# io_board.net
KiCad netlist of a schematic drawn in EAGLE
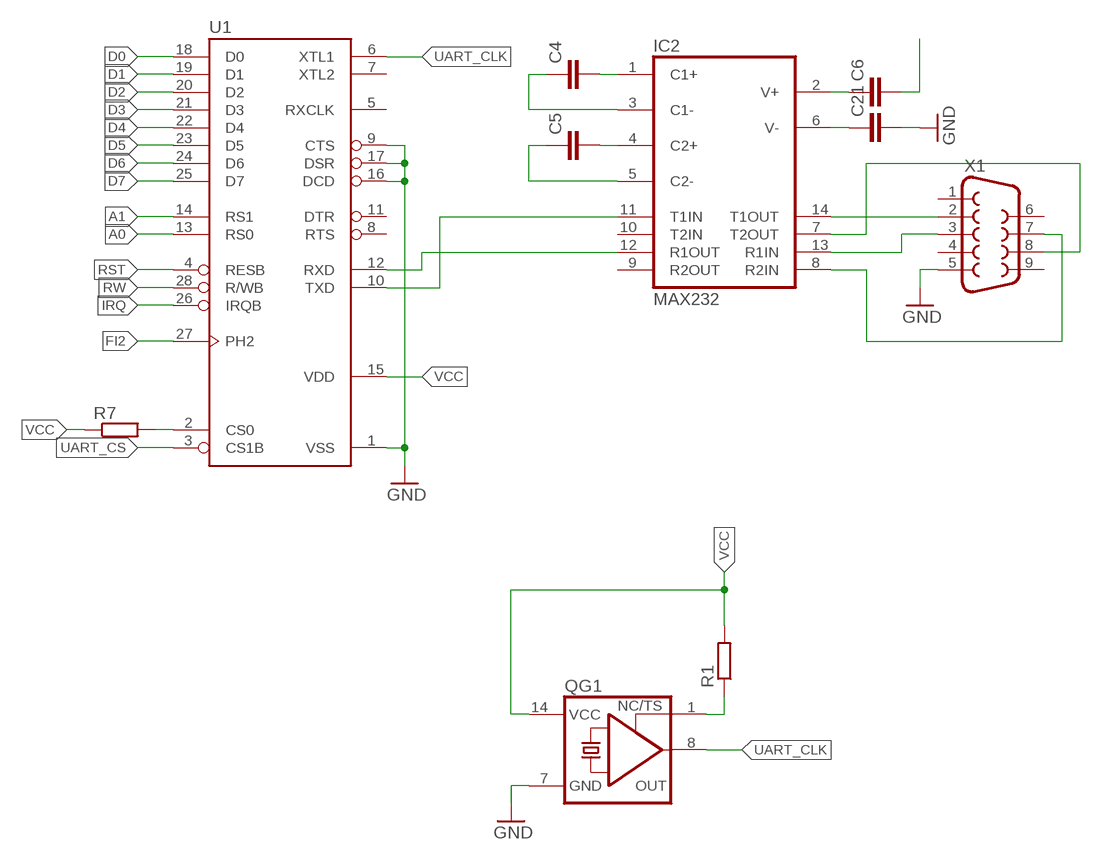
[diagram p0: schematic, sheet 1, part 1 of 2]
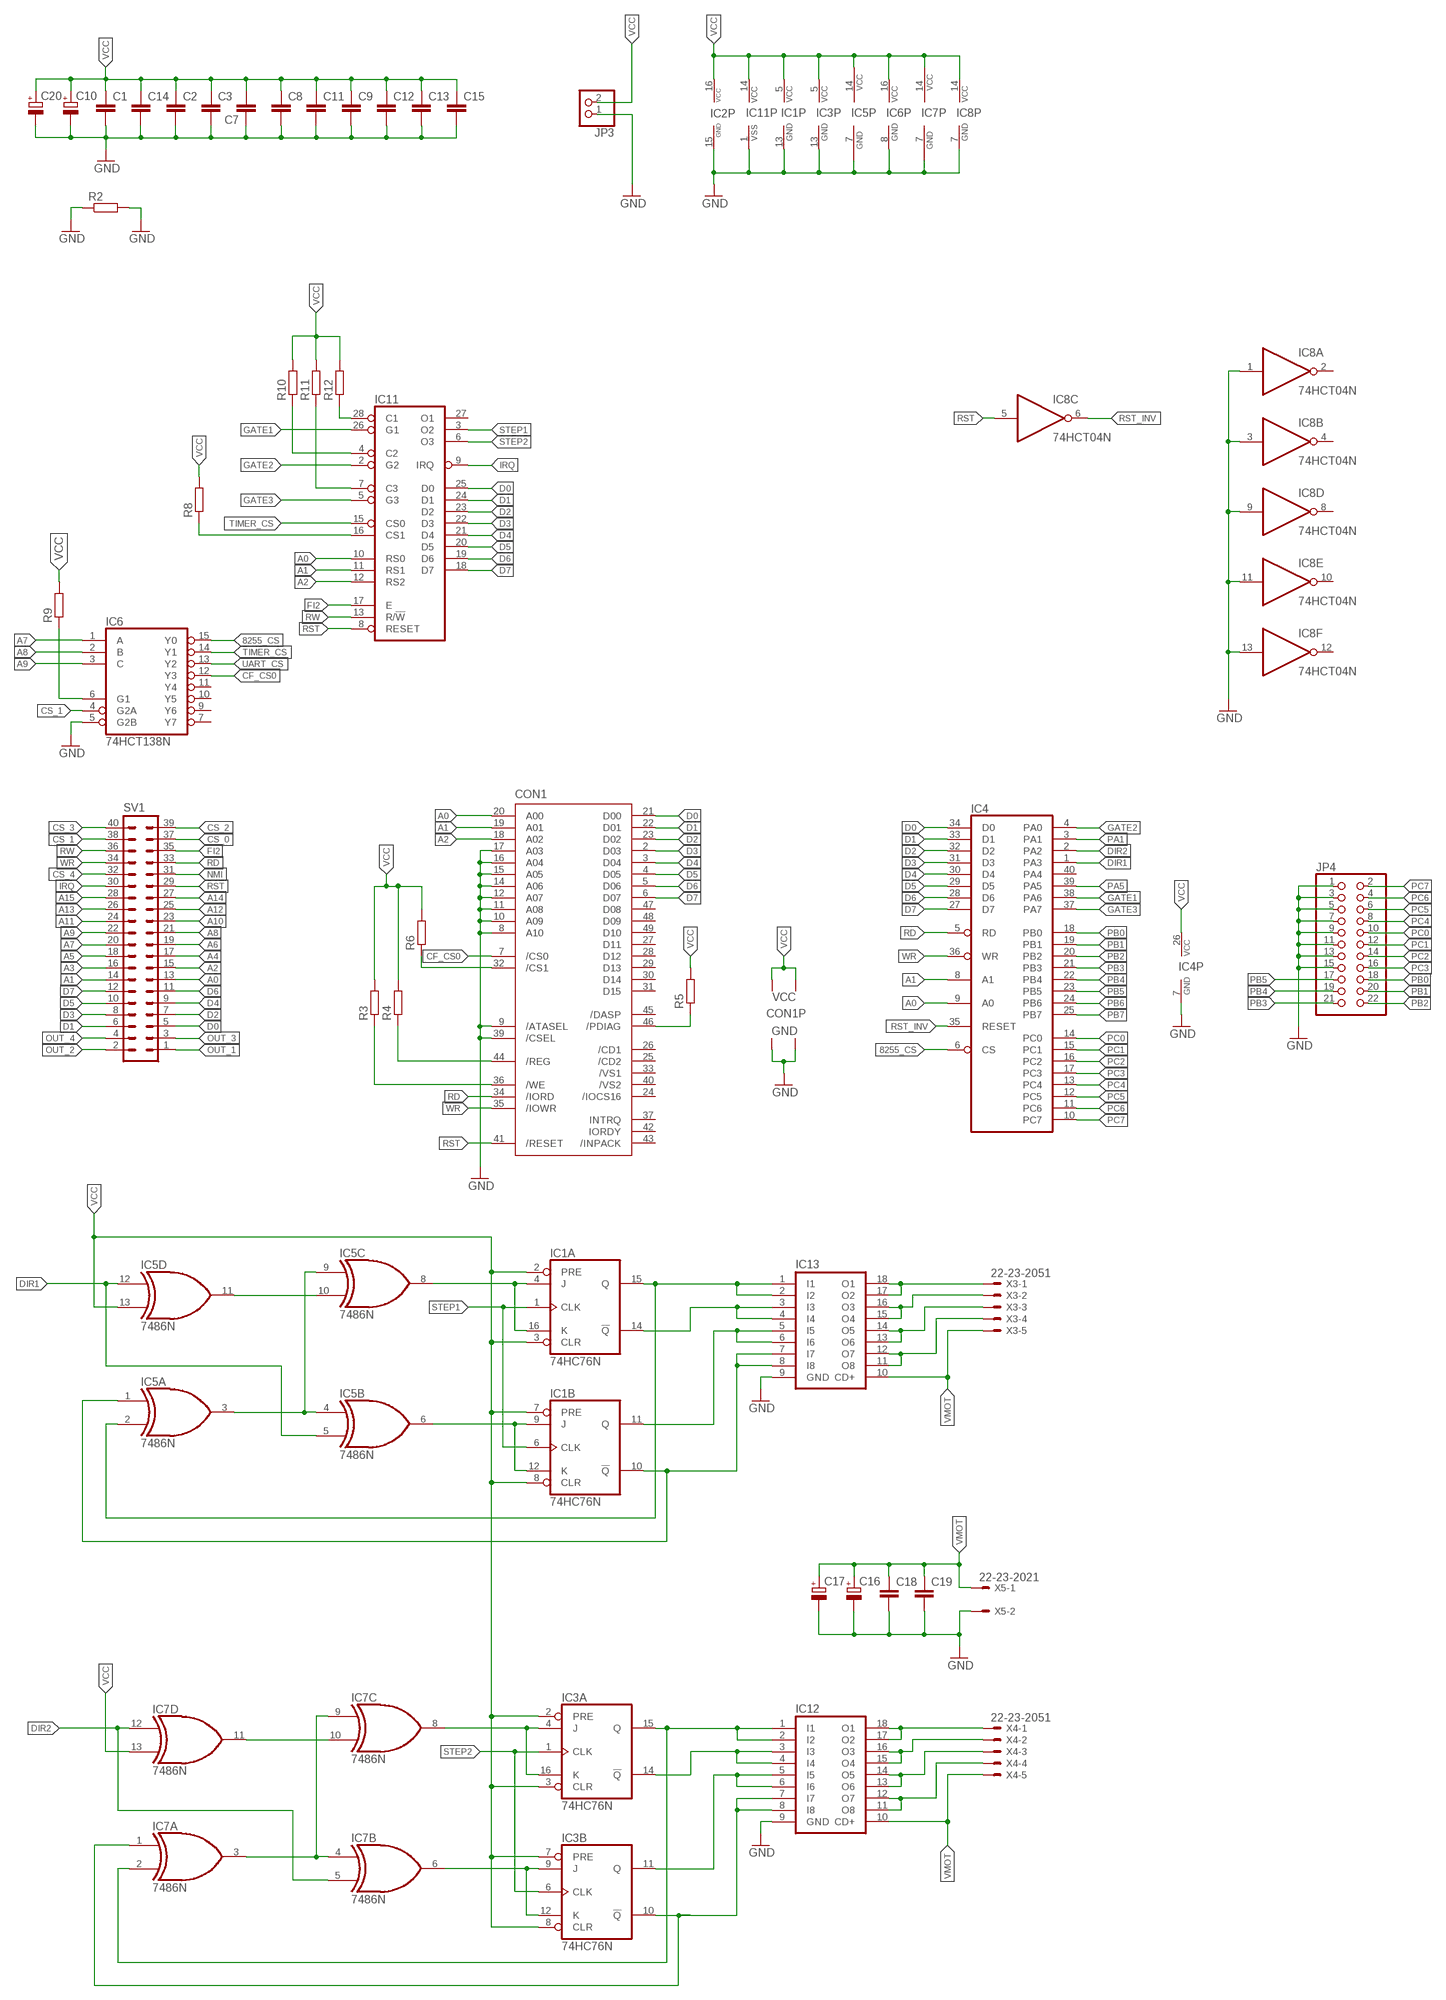
[diagram p1: schematic, sheet 1, part 2 of 2]

(export (version "E")
  (design (tool "Eeschema 10.0.6"))
  (components
    (comp (ref "C1")
      (value "C-EUC1206")
      (footprint "eagle-import:C1206")
      (libsource (lib "eagle-import") (part "C-EUC1206"))
    )
    (comp (ref "C2")
      (value "C-EUC1206")
      (footprint "eagle-import:C1206")
      (libsource (lib "eagle-import") (part "C-EUC1206"))
    )
    (comp (ref "C3")
      (value "C-EUC1206")
      (footprint "eagle-import:C1206")
      (libsource (lib "eagle-import") (part "C-EUC1206"))
    )
    (comp (ref "C4")
      (value "C-EUC0603")
      (footprint "eagle-import:C0603")
      (libsource (lib "eagle-import") (part "C-EUC0603"))
    )
    (comp (ref "C5")
      (value "C-EUC0603")
      (footprint "eagle-import:C0603")
      (libsource (lib "eagle-import") (part "C-EUC0603"))
    )
    (comp (ref "C6")
      (value "C-EUC0603")
      (footprint "eagle-import:C0603")
      (libsource (lib "eagle-import") (part "C-EUC0603"))
    )
    (comp (ref "C7")
      (value "C-EUC0603")
      (footprint "eagle-import:C0603")
      (libsource (lib "eagle-import") (part "C-EUC0603"))
    )
    (comp (ref "C8")
      (value "C-EUC0603")
      (footprint "eagle-import:C0603")
      (libsource (lib "eagle-import") (part "C-EUC0603"))
    )
    (comp (ref "C9")
      (value "C-EUC0603")
      (footprint "eagle-import:C0603")
      (libsource (lib "eagle-import") (part "C-EUC0603"))
    )
    (comp (ref "C10")
      (value "CPOL-EUE5-10.5")
      (footprint "eagle-import:E5-10,5")
      (libsource (lib "eagle-import") (part "CPOL-EUE5-10.5"))
    )
    (comp (ref "C11")
      (value "C-EU050-024X044")
      (footprint "eagle-import:C050-024X044")
      (libsource (lib "eagle-import") (part "C-EU050-024X044"))
    )
    (comp (ref "C12")
      (value "C-EUC0603")
      (footprint "eagle-import:C0603")
      (libsource (lib "eagle-import") (part "C-EUC0603"))
    )
    (comp (ref "C13")
      (value "C-EUC0603")
      (footprint "eagle-import:C0603")
      (libsource (lib "eagle-import") (part "C-EUC0603"))
    )
    (comp (ref "C14")
      (value "C-EUC1206")
      (footprint "eagle-import:C1206")
      (libsource (lib "eagle-import") (part "C-EUC1206"))
    )
    (comp (ref "C15")
      (value "C-EUC0603")
      (footprint "eagle-import:C0603")
      (libsource (lib "eagle-import") (part "C-EUC0603"))
    )
    (comp (ref "C16")
      (value "CPOL-EUE5-6")
      (footprint "eagle-import:E5-6")
      (libsource (lib "eagle-import") (part "CPOL-EUE5-6"))
    )
    (comp (ref "C17")
      (value "CPOL-EUE5-6")
      (footprint "eagle-import:E5-6")
      (libsource (lib "eagle-import") (part "CPOL-EUE5-6"))
    )
    (comp (ref "C18")
      (value "C-EUC0603")
      (footprint "eagle-import:C0603")
      (libsource (lib "eagle-import") (part "C-EUC0603"))
    )
    (comp (ref "C19")
      (value "C-EUC0603")
      (footprint "eagle-import:C0603")
      (libsource (lib "eagle-import") (part "C-EUC0603"))
    )
    (comp (ref "C20")
      (value "CPOL-EUSMCB")
      (footprint "eagle-import:SMC_B")
      (libsource (lib "eagle-import") (part "CPOL-EUSMCB"))
    )
    (comp (ref "C21")
      (value "C-EUC0603")
      (footprint "eagle-import:C0603")
      (libsource (lib "eagle-import") (part "C-EUC0603"))
    )
    (comp (ref "CON1")
      (value "CF-CARD-IDE_MODE")
      (footprint "eagle-import:MI20-50PD-SF")
      (libsource (lib "eagle-import") (part "CF-CARD-IDE_MODE"))
    )
    (comp (ref "IC1")
      (value "74HC76N")
      (footprint "eagle-import:DIL16")
      (libsource (lib "eagle-import") (part "7476NHC"))
    )
    (comp (ref "IC2")
      (value "MAX232")
      (footprint "eagle-import:DIL16")
      (fields (field (name "MF") "MAXIM") (field (name "MPN") "MAX232ACPE+"))
      (libsource (lib "eagle-import") (part "MAX232"))
    )
    (comp (ref "IC3")
      (value "74HC76N")
      (footprint "eagle-import:DIL16")
      (libsource (lib "eagle-import") (part "7476NHC"))
    )
    (comp (ref "IC4")
      (value "8255A")
      (footprint "eagle-import:DIL40")
      (libsource (lib "eagle-import") (part "8255A"))
    )
    (comp (ref "IC5")
      (value "7486N")
      (footprint "eagle-import:DIL14")
      (libsource (lib "eagle-import") (part "7486N"))
    )
    (comp (ref "IC6")
      (value "74HCT138N")
      (footprint "eagle-import:DIL16")
      (libsource (lib "eagle-import") (part "74138NHCT"))
    )
    (comp (ref "IC7")
      (value "7486N")
      (footprint "eagle-import:DIL14")
      (libsource (lib "eagle-import") (part "7486N"))
    )
    (comp (ref "IC8")
      (value "74HCT04N")
      (footprint "eagle-import:DIL14")
      (libsource (lib "eagle-import") (part "7404NHCT"))
    )
    (comp (ref "IC11")
      (value "6840")
      (footprint "eagle-import:DIL28")
      (libsource (lib "eagle-import") (part "6840"))
    )
    (comp (ref "IC12")
      (value "ULN2803A")
      (footprint "eagle-import:DIL18")
      (libsource (lib "eagle-import") (part "ULN2803A"))
    )
    (comp (ref "IC13")
      (value "ULN2803A")
      (footprint "eagle-import:DIL18")
      (libsource (lib "eagle-import") (part "ULN2803A"))
    )
    (comp (ref "JP3")
      (value "PINHD-1X2/90")
      (footprint "eagle-import:1X02_90")
      (libsource (lib "eagle-import") (part "PINHD-1X2/90"))
    )
    (comp (ref "JP4")
      (value "PINHD-2X11")
      (footprint "eagle-import:2X11")
      (libsource (lib "eagle-import") (part "PINHD-2X11"))
    )
    (comp (ref "QG1")
      (value "XO-14")
      (footprint "eagle-import:DIL14S")
      (libsource (lib "eagle-import") (part "XO-14"))
    )
    (comp (ref "R1")
      (value "R-EU_R1206")
      (footprint "eagle-import:R1206")
      (libsource (lib "eagle-import") (part "R-EU_R1206"))
    )
    (comp (ref "R2")
      (value "R-EU_M1206")
      (footprint "eagle-import:M1206")
      (libsource (lib "eagle-import") (part "R-EU_M1206"))
    )
    (comp (ref "R3")
      (value "R-EU_R0603")
      (footprint "eagle-import:R0603")
      (libsource (lib "eagle-import") (part "R-EU_R0603"))
    )
    (comp (ref "R4")
      (value "R-EU_R0603")
      (footprint "eagle-import:R0603")
      (libsource (lib "eagle-import") (part "R-EU_R0603"))
    )
    (comp (ref "R5")
      (value "R-EU_R0603")
      (footprint "eagle-import:R0603")
      (libsource (lib "eagle-import") (part "R-EU_R0603"))
    )
    (comp (ref "R6")
      (value "R-EU_R0603")
      (footprint "eagle-import:R0603")
      (libsource (lib "eagle-import") (part "R-EU_R0603"))
    )
    (comp (ref "R7")
      (value "R-EU_R0603")
      (footprint "eagle-import:R0603")
      (libsource (lib "eagle-import") (part "R-EU_R0603"))
    )
    (comp (ref "R8")
      (value "R-EU_R0402")
      (footprint "eagle-import:R0402")
      (libsource (lib "eagle-import") (part "R-EU_R0402"))
    )
    (comp (ref "R9")
      (value "R-EU_R1206")
      (footprint "eagle-import:R1206")
      (libsource (lib "eagle-import") (part "R-EU_R1206"))
    )
    (comp (ref "R10")
      (value "R-EU_R0603")
      (footprint "eagle-import:R0603")
      (libsource (lib "eagle-import") (part "R-EU_R0603"))
    )
    (comp (ref "R11")
      (value "R-EU_0204/7")
      (footprint "eagle-import:0204_7")
      (libsource (lib "eagle-import") (part "R-EU_0204/7"))
    )
    (comp (ref "R12")
      (value "R-EU_0204/5")
      (footprint "eagle-import:0204_5")
      (libsource (lib "eagle-import") (part "R-EU_0204/5"))
    )
    (comp (ref "SV1")
      (value "ML40L")
      (footprint "eagle-import:ML40L")
      (libsource (lib "eagle-import") (part "ML40L"))
    )
    (comp (ref "U1")
      (value "G65SC51P")
      (footprint "eagle-import:DIP-28")
      (libsource (lib "eagle-import") (part "G65SC51P"))
    )
    (comp (ref "X1")
      (value "F09HP")
      (footprint "eagle-import:F09HP")
      (libsource (lib "eagle-import") (part "F09HP"))
    )
    (comp (ref "X3")
      (value "22-23-2051")
      (footprint "eagle-import:22-23-2051")
      (fields (field (name "MF") "MOLEX"))
      (libsource (lib "eagle-import") (part "22-23-2051"))
    )
    (comp (ref "X4")
      (value "22-23-2051")
      (footprint "eagle-import:22-23-2051")
      (fields (field (name "MF") "MOLEX"))
      (libsource (lib "eagle-import") (part "22-23-2051"))
    )
    (comp (ref "X5")
      (value "22-23-2021")
      (footprint "eagle-import:22-23-2021")
      (fields (field (name "MF") "MOLEX"))
      (libsource (lib "eagle-import") (part "22-23-2021"))
    )
  )
  (nets
    (net (code "1") (name "8255_CS") (class "Default")
      (node (ref "IC4") (pin "6") (pinfunction "CS_6") (pintype "input"))
      (node (ref "IC6") (pin "15") (pinfunction "Y0_15") (pintype "output"))
    )
    (net (code "2") (name "A0") (class "Default")
      (node (ref "CON1") (pin "20") (pinfunction "A00_20") (pintype "input"))
      (node (ref "IC11") (pin "10") (pinfunction "RS0_10") (pintype "input"))
      (node (ref "IC4") (pin "9") (pinfunction "A0_9") (pintype "input"))
      (node (ref "SV1") (pin "13") (pinfunction "13_13") (pintype "passive"))
      (node (ref "U1") (pin "13") (pinfunction "RS0_13") (pintype "input"))
    )
    (net (code "3") (name "A1") (class "Default")
      (node (ref "CON1") (pin "19") (pinfunction "A01_19") (pintype "input"))
      (node (ref "IC11") (pin "11") (pinfunction "RS1_11") (pintype "input"))
      (node (ref "IC4") (pin "8") (pinfunction "A1_8") (pintype "input"))
      (node (ref "SV1") (pin "14") (pinfunction "14_14") (pintype "passive"))
      (node (ref "U1") (pin "14") (pinfunction "RS1_14") (pintype "input"))
    )
    (net (code "4") (name "A2") (class "Default")
      (node (ref "CON1") (pin "18") (pinfunction "A02_18") (pintype "input"))
      (node (ref "IC11") (pin "12") (pinfunction "RS2_12") (pintype "input"))
      (node (ref "SV1") (pin "15") (pinfunction "15_15") (pintype "passive"))
    )
    (net (code "5") (name "A3") (class "Default")
      (node (ref "SV1") (pin "16") (pinfunction "16_16") (pintype "passive"))
    )
    (net (code "6") (name "A4") (class "Default")
      (node (ref "SV1") (pin "17") (pinfunction "17_17") (pintype "passive"))
    )
    (net (code "7") (name "A5") (class "Default")
      (node (ref "SV1") (pin "18") (pinfunction "18_18") (pintype "passive"))
    )
    (net (code "8") (name "A6") (class "Default")
      (node (ref "SV1") (pin "19") (pinfunction "19_19") (pintype "passive"))
    )
    (net (code "9") (name "A7") (class "Default")
      (node (ref "IC6") (pin "1") (pinfunction "A_1") (pintype "input"))
      (node (ref "SV1") (pin "20") (pinfunction "20_20") (pintype "passive"))
    )
    (net (code "10") (name "A8") (class "Default")
      (node (ref "IC6") (pin "2") (pinfunction "B_2") (pintype "input"))
      (node (ref "SV1") (pin "21") (pinfunction "21_21") (pintype "passive"))
    )
    (net (code "11") (name "A9") (class "Default")
      (node (ref "IC6") (pin "3") (pinfunction "C_3") (pintype "input"))
      (node (ref "SV1") (pin "22") (pinfunction "22_22") (pintype "passive"))
    )
    (net (code "12") (name "A10") (class "Default")
      (node (ref "SV1") (pin "23") (pinfunction "23_23") (pintype "passive"))
    )
    (net (code "13") (name "A11") (class "Default")
      (node (ref "SV1") (pin "24") (pinfunction "24_24") (pintype "passive"))
    )
    (net (code "14") (name "A12") (class "Default")
      (node (ref "SV1") (pin "25") (pinfunction "25_25") (pintype "passive"))
    )
    (net (code "15") (name "A13") (class "Default")
      (node (ref "SV1") (pin "26") (pinfunction "26_26") (pintype "passive"))
    )
    (net (code "16") (name "A14") (class "Default")
      (node (ref "SV1") (pin "27") (pinfunction "27_27") (pintype "passive"))
    )
    (net (code "17") (name "A15") (class "Default")
      (node (ref "SV1") (pin "28") (pinfunction "28_28") (pintype "passive"))
    )
    (net (code "18") (name "CF_CS0") (class "Default")
      (node (ref "CON1") (pin "7") (pinfunction "/CS0_7") (pintype "input"))
      (node (ref "IC6") (pin "12") (pinfunction "Y3_12") (pintype "output"))
    )
    (net (code "19") (name "CS_0") (class "Default")
      (node (ref "SV1") (pin "37") (pinfunction "37_37") (pintype "passive"))
    )
    (net (code "20") (name "CS_1") (class "Default")
      (node (ref "IC6") (pin "4") (pinfunction "G2A_4") (pintype "input"))
      (node (ref "SV1") (pin "38") (pinfunction "38_38") (pintype "passive"))
    )
    (net (code "21") (name "CS_2") (class "Default")
      (node (ref "SV1") (pin "39") (pinfunction "39_39") (pintype "passive"))
    )
    (net (code "22") (name "CS_3") (class "Default")
      (node (ref "SV1") (pin "40") (pinfunction "40_40") (pintype "passive"))
    )
    (net (code "23") (name "CS_4") (class "Default")
      (node (ref "SV1") (pin "32") (pinfunction "32_32") (pintype "passive"))
    )
    (net (code "24") (name "D0") (class "Default")
      (node (ref "CON1") (pin "21") (pinfunction "D00_21") (pintype "bidirectional"))
      (node (ref "IC11") (pin "25") (pinfunction "D0_25") (pintype "bidirectional"))
      (node (ref "IC4") (pin "34") (pinfunction "D0_34") (pintype "bidirectional"))
      (node (ref "SV1") (pin "5") (pinfunction "5_5") (pintype "passive"))
      (node (ref "U1") (pin "18") (pinfunction "D0_18") (pintype "bidirectional"))
    )
    (net (code "25") (name "D1") (class "Default")
      (node (ref "CON1") (pin "22") (pinfunction "D01_22") (pintype "bidirectional"))
      (node (ref "IC11") (pin "24") (pinfunction "D1_24") (pintype "bidirectional"))
      (node (ref "IC4") (pin "33") (pinfunction "D1_33") (pintype "bidirectional"))
      (node (ref "SV1") (pin "6") (pinfunction "6_6") (pintype "passive"))
      (node (ref "U1") (pin "19") (pinfunction "D1_19") (pintype "bidirectional"))
    )
    (net (code "26") (name "D2") (class "Default")
      (node (ref "CON1") (pin "23") (pinfunction "D02_23") (pintype "bidirectional"))
      (node (ref "IC11") (pin "23") (pinfunction "D2_23") (pintype "bidirectional"))
      (node (ref "IC4") (pin "32") (pinfunction "D2_32") (pintype "bidirectional"))
      (node (ref "SV1") (pin "7") (pinfunction "7_7") (pintype "passive"))
      (node (ref "U1") (pin "20") (pinfunction "D2_20") (pintype "bidirectional"))
    )
    (net (code "27") (name "D3") (class "Default")
      (node (ref "CON1") (pin "2") (pinfunction "D03_2") (pintype "bidirectional"))
      (node (ref "IC11") (pin "22") (pinfunction "D3_22") (pintype "bidirectional"))
      (node (ref "IC4") (pin "31") (pinfunction "D3_31") (pintype "bidirectional"))
      (node (ref "SV1") (pin "8") (pinfunction "8_8") (pintype "passive"))
      (node (ref "U1") (pin "21") (pinfunction "D3_21") (pintype "bidirectional"))
    )
    (net (code "28") (name "D4") (class "Default")
      (node (ref "CON1") (pin "3") (pinfunction "D04_3") (pintype "bidirectional"))
      (node (ref "IC11") (pin "21") (pinfunction "D4_21") (pintype "bidirectional"))
      (node (ref "IC4") (pin "30") (pinfunction "D4_30") (pintype "bidirectional"))
      (node (ref "SV1") (pin "9") (pinfunction "9_9") (pintype "passive"))
      (node (ref "U1") (pin "22") (pinfunction "D4_22") (pintype "bidirectional"))
    )
    (net (code "29") (name "D5") (class "Default")
      (node (ref "CON1") (pin "4") (pinfunction "D05_4") (pintype "bidirectional"))
      (node (ref "IC11") (pin "20") (pinfunction "D5_20") (pintype "bidirectional"))
      (node (ref "IC4") (pin "29") (pinfunction "D5_29") (pintype "bidirectional"))
      (node (ref "SV1") (pin "10") (pinfunction "10_10") (pintype "passive"))
      (node (ref "U1") (pin "23") (pinfunction "D5_23") (pintype "bidirectional"))
    )
    (net (code "30") (name "D6") (class "Default")
      (node (ref "CON1") (pin "5") (pinfunction "D06_5") (pintype "bidirectional"))
      (node (ref "IC11") (pin "19") (pinfunction "D6_19") (pintype "bidirectional"))
      (node (ref "IC4") (pin "28") (pinfunction "D6_28") (pintype "bidirectional"))
      (node (ref "SV1") (pin "11") (pinfunction "11_11") (pintype "passive"))
      (node (ref "U1") (pin "24") (pinfunction "D6_24") (pintype "bidirectional"))
    )
    (net (code "31") (name "D7") (class "Default")
      (node (ref "CON1") (pin "6") (pinfunction "D07_6") (pintype "bidirectional"))
      (node (ref "IC11") (pin "18") (pinfunction "D7_18") (pintype "bidirectional"))
      (node (ref "IC4") (pin "27") (pinfunction "D7_27") (pintype "bidirectional"))
      (node (ref "SV1") (pin "12") (pinfunction "12_12") (pintype "passive"))
      (node (ref "U1") (pin "25") (pinfunction "D7_25") (pintype "bidirectional"))
    )
    (net (code "32") (name "DIR1") (class "Default")
      (node (ref "IC4") (pin "1") (pinfunction "PA3_1") (pintype "bidirectional"))
      (node (ref "IC5") (pin "12") (pinfunction "I0_12") (pintype "input"))
      (node (ref "IC5") (pin "5") (pinfunction "I1_5") (pintype "input"))
    )
    (net (code "33") (name "DIR2") (class "Default")
      (node (ref "IC4") (pin "2") (pinfunction "PA2_2") (pintype "bidirectional"))
      (node (ref "IC7") (pin "12") (pinfunction "I0_12") (pintype "input"))
      (node (ref "IC7") (pin "5") (pinfunction "I1_5") (pintype "input"))
    )
    (net (code "34") (name "FI2") (class "Default")
      (node (ref "IC11") (pin "17") (pinfunction "E_17") (pintype "input"))
      (node (ref "SV1") (pin "35") (pinfunction "35_35") (pintype "passive"))
      (node (ref "U1") (pin "27") (pinfunction "PH2_27") (pintype "power_in"))
    )
    (net (code "35") (name "GATE1") (class "Default")
      (node (ref "IC11") (pin "26") (pinfunction "G1_26") (pintype "input"))
      (node (ref "IC4") (pin "38") (pinfunction "PA6_38") (pintype "bidirectional"))
    )
    (net (code "36") (name "GATE2") (class "Default")
      (node (ref "IC11") (pin "2") (pinfunction "G2_2") (pintype "input"))
      (node (ref "IC4") (pin "4") (pinfunction "PA0_4") (pintype "bidirectional"))
    )
    (net (code "37") (name "GATE3") (class "Default")
      (node (ref "IC11") (pin "5") (pinfunction "G3_5") (pintype "input"))
      (node (ref "IC4") (pin "37") (pinfunction "PA7_37") (pintype "bidirectional"))
    )
    (net (code "38") (name "GND") (class "Default")
      (node (ref "C1") (pin "2") (pinfunction "2_2") (pintype "passive"))
      (node (ref "C10") (pin "-") (pinfunction "-_-") (pintype "passive"))
      (node (ref "C11") (pin "2") (pinfunction "2_2") (pintype "passive"))
      (node (ref "C12") (pin "2") (pinfunction "2_2") (pintype "passive"))
      (node (ref "C13") (pin "2") (pinfunction "2_2") (pintype "passive"))
      (node (ref "C14") (pin "2") (pinfunction "2_2") (pintype "passive"))
      (node (ref "C15") (pin "2") (pinfunction "2_2") (pintype "passive"))
      (node (ref "C16") (pin "-") (pinfunction "-_-") (pintype "passive"))
      (node (ref "C17") (pin "-") (pinfunction "-_-") (pintype "passive"))
      (node (ref "C18") (pin "2") (pinfunction "2_2") (pintype "passive"))
      (node (ref "C19") (pin "2") (pinfunction "2_2") (pintype "passive"))
      (node (ref "C2") (pin "2") (pinfunction "2_2") (pintype "passive"))
      (node (ref "C20") (pin "-") (pinfunction "-_-") (pintype "passive"))
      (node (ref "C21") (pin "2") (pinfunction "2_2") (pintype "passive"))
      (node (ref "C3") (pin "2") (pinfunction "2_2") (pintype "passive"))
      (node (ref "C7") (pin "1") (pinfunction "1_1") (pintype "passive"))
      (node (ref "C8") (pin "2") (pinfunction "2_2") (pintype "passive"))
      (node (ref "C9") (pin "2") (pinfunction "2_2") (pintype "passive"))
      (node (ref "CON1") (pin "1") (pinfunction "GND1_1") (pintype "power_in"))
      (node (ref "CON1") (pin "10") (pinfunction "A09_10") (pintype "input"))
      (node (ref "CON1") (pin "11") (pinfunction "A08_11") (pintype "input"))
      (node (ref "CON1") (pin "12") (pinfunction "A07_12") (pintype "input"))
      (node (ref "CON1") (pin "14") (pinfunction "A06_14") (pintype "input"))
      (node (ref "CON1") (pin "15") (pinfunction "A05_15") (pintype "input"))
      (node (ref "CON1") (pin "16") (pinfunction "A04_16") (pintype "input"))
      (node (ref "CON1") (pin "17") (pinfunction "A03_17") (pintype "input"))
      (node (ref "CON1") (pin "39") (pinfunction "/CSEL_39") (pintype "input"))
      (node (ref "CON1") (pin "50") (pinfunction "GND2_50") (pintype "power_in"))
      (node (ref "CON1") (pin "8") (pinfunction "A10_8") (pintype "input"))
      (node (ref "CON1") (pin "9") (pinfunction "/ATASEL_9") (pintype "input"))
      (node (ref "IC1") (pin "13") (pinfunction "GND_13") (pintype "power_in"))
      (node (ref "IC11") (pin "1") (pinfunction "VSS_1") (pintype "power_in"))
      (node (ref "IC12") (pin "9") (pinfunction "GND_9") (pintype "power_in"))
      (node (ref "IC13") (pin "9") (pinfunction "GND_9") (pintype "power_in"))
      (node (ref "IC2") (pin "15") (pinfunction "GND_15") (pintype "power_in"))
      (node (ref "IC3") (pin "13") (pinfunction "GND_13") (pintype "power_in"))
      (node (ref "IC4") (pin "7") (pinfunction "GND_7") (pintype "power_in"))
      (node (ref "IC5") (pin "7") (pinfunction "GND_7") (pintype "power_in"))
      (node (ref "IC6") (pin "5") (pinfunction "G2B_5") (pintype "input"))
      (node (ref "IC6") (pin "8") (pinfunction "GND_8") (pintype "power_in"))
      (node (ref "IC7") (pin "7") (pinfunction "GND_7") (pintype "power_in"))
      (node (ref "IC8") (pin "1") (pinfunction "I_1") (pintype "input"))
      (node (ref "IC8") (pin "11") (pinfunction "I_11") (pintype "input"))
      (node (ref "IC8") (pin "13") (pinfunction "I_13") (pintype "input"))
      (node (ref "IC8") (pin "3") (pinfunction "I_3") (pintype "input"))
      (node (ref "IC8") (pin "7") (pinfunction "GND_7") (pintype "power_in"))
      (node (ref "IC8") (pin "9") (pinfunction "I_9") (pintype "input"))
      (node (ref "JP3") (pin "1") (pinfunction "1_1") (pintype "passive"))
      (node (ref "JP4") (pin "1") (pinfunction "1_1") (pintype "passive"))
      (node (ref "JP4") (pin "11") (pinfunction "11_11") (pintype "passive"))
      (node (ref "JP4") (pin "13") (pinfunction "13_13") (pintype "passive"))
      (node (ref "JP4") (pin "15") (pinfunction "15_15") (pintype "passive"))
      (node (ref "JP4") (pin "3") (pinfunction "3_3") (pintype "passive"))
      (node (ref "JP4") (pin "5") (pinfunction "5_5") (pintype "passive"))
      (node (ref "JP4") (pin "7") (pinfunction "7_7") (pintype "passive"))
      (node (ref "JP4") (pin "9") (pinfunction "9_9") (pintype "passive"))
      (node (ref "QG1") (pin "7") (pinfunction "GND_7") (pintype "power_in"))
      (node (ref "R2") (pin "1") (pinfunction "1_1") (pintype "passive"))
      (node (ref "R2") (pin "2") (pinfunction "2_2") (pintype "passive"))
      (node (ref "U1") (pin "1") (pinfunction "VSS_1") (pintype "power_in"))
      (node (ref "U1") (pin "16") (pinfunction "DCD_16") (pintype "input"))
      (node (ref "U1") (pin "17") (pinfunction "DSR_17") (pintype "input"))
      (node (ref "U1") (pin "9") (pinfunction "CTS_9") (pintype "input"))
      (node (ref "X1") (pin "5") (pinfunction "5_5") (pintype "passive"))
      (node (ref "X5") (pin "2") (pinfunction "S_2") (pintype "passive"))
    )
    (net (code "39") (name "IRQ") (class "Default")
      (node (ref "IC11") (pin "9") (pinfunction "IRQ_9") (pintype "open_collector"))
      (node (ref "SV1") (pin "30") (pinfunction "30_30") (pintype "passive"))
      (node (ref "U1") (pin "26") (pinfunction "IRQB_26") (pintype "output"))
    )
    (net (code "40") (name "NMI") (class "Default")
      (node (ref "SV1") (pin "31") (pinfunction "31_31") (pintype "passive"))
    )
    (net (code "41") (name "Net-(CON1A-{slash}CS1)") (class "Default")
      (node (ref "CON1") (pin "32") (pinfunction "/CS1_32") (pintype "input"))
      (node (ref "R6") (pin "1") (pinfunction "1_1") (pintype "passive"))
    )
    (net (code "42") (name "Net-(CON1A-{slash}PDIAG)") (class "Default")
      (node (ref "CON1") (pin "46") (pinfunction "/PDIAG_46") (pintype "bidirectional"))
      (node (ref "R5") (pin "1") (pinfunction "1_1") (pintype "passive"))
    )
    (net (code "43") (name "Net-(CON1A-{slash}REG)") (class "Default")
      (node (ref "CON1") (pin "44") (pinfunction "/REG_44") (pintype "input"))
      (node (ref "R4") (pin "1") (pinfunction "1_1") (pintype "passive"))
    )
    (net (code "44") (name "Net-(CON1A-{slash}WE)") (class "Default")
      (node (ref "CON1") (pin "36") (pinfunction "/WE_36") (pintype "input"))
      (node (ref "R3") (pin "1") (pinfunction "1_1") (pintype "passive"))
    )
    (net (code "45") (name "Net-(IC1A-J)") (class "Default")
      (node (ref "IC1") (pin "16") (pinfunction "K_16") (pintype "input"))
      (node (ref "IC1") (pin "4") (pinfunction "J_4") (pintype "input"))
      (node (ref "IC5") (pin "8") (pinfunction "O_8") (pintype "output"))
    )
    (net (code "46") (name "Net-(IC1B-J)") (class "Default")
      (node (ref "IC1") (pin "12") (pinfunction "K_12") (pintype "input"))
      (node (ref "IC1") (pin "9") (pinfunction "J_9") (pintype "input"))
      (node (ref "IC5") (pin "6") (pinfunction "O_6") (pintype "output"))
    )
    (net (code "47") (name "Net-(IC2A-C1+)") (class "Default")
      (node (ref "C4") (pin "2") (pinfunction "2_2") (pintype "passive"))
      (node (ref "IC2") (pin "1") (pinfunction "C1+_1") (pintype "bidirectional"))
    )
    (net (code "48") (name "Net-(IC2A-C1-)") (class "Default")
      (node (ref "C4") (pin "1") (pinfunction "1_1") (pintype "passive"))
      (node (ref "IC2") (pin "3") (pinfunction "C1-_3") (pintype "bidirectional"))
    )
    (net (code "49") (name "Net-(IC2A-C2+)") (class "Default")
      (node (ref "C5") (pin "2") (pinfunction "2_2") (pintype "passive"))
      (node (ref "IC2") (pin "4") (pinfunction "C2+_4") (pintype "bidirectional"))
    )
    (net (code "50") (name "Net-(IC2A-C2-)") (class "Default")
      (node (ref "C5") (pin "1") (pinfunction "1_1") (pintype "passive"))
      (node (ref "IC2") (pin "5") (pinfunction "C2-_5") (pintype "bidirectional"))
    )
    (net (code "51") (name "Net-(IC2A-R1IN)") (class "Default")
      (node (ref "IC2") (pin "13") (pinfunction "R1IN_13") (pintype "input"))
      (node (ref "X1") (pin "3") (pinfunction "3_3") (pintype "passive"))
    )
    (net (code "52") (name "Net-(IC2A-R1OUT)") (class "Default")
      (node (ref "IC2") (pin "12") (pinfunction "R1OUT_12") (pintype "output"))
      (node (ref "U1") (pin "12") (pinfunction "RXD_12") (pintype "input"))
    )
    (net (code "53") (name "Net-(IC2A-R2IN)") (class "Default")
      (node (ref "IC2") (pin "8") (pinfunction "R2IN_8") (pintype "input"))
      (node (ref "X1") (pin "7") (pinfunction "7_7") (pintype "passive"))
    )
    (net (code "54") (name "Net-(IC2A-T1IN)") (class "Default")
      (node (ref "IC2") (pin "11") (pinfunction "T1IN_11") (pintype "input"))
      (node (ref "U1") (pin "10") (pinfunction "TXD_10") (pintype "output"))
    )
    (net (code "55") (name "Net-(IC2A-T1OUT)") (class "Default")
      (node (ref "IC2") (pin "14") (pinfunction "T1OUT_14") (pintype "output"))
      (node (ref "X1") (pin "2") (pinfunction "2_2") (pintype "passive"))
    )
    (net (code "56") (name "Net-(IC2A-T2OUT)") (class "Default")
      (node (ref "IC2") (pin "7") (pinfunction "T2OUT_7") (pintype "output"))
      (node (ref "X1") (pin "8") (pinfunction "8_8") (pintype "passive"))
    )
    (net (code "57") (name "Net-(IC2A-V+)") (class "Default")
      (node (ref "C6") (pin "1") (pinfunction "1_1") (pintype "passive"))
      (node (ref "IC2") (pin "2") (pinfunction "V+_2") (pintype "bidirectional"))
    )
    (net (code "58") (name "Net-(IC2A-V-)") (class "Default")
      (node (ref "C21") (pin "1") (pinfunction "1_1") (pintype "passive"))
      (node (ref "IC2") (pin "6") (pinfunction "V-_6") (pintype "bidirectional"))
    )
    (net (code "59") (name "Net-(IC3A-J)") (class "Default")
      (node (ref "IC3") (pin "16") (pinfunction "K_16") (pintype "input"))
      (node (ref "IC3") (pin "4") (pinfunction "J_4") (pintype "input"))
      (node (ref "IC7") (pin "8") (pinfunction "O_8") (pintype "output"))
    )
    (net (code "60") (name "Net-(IC3B-J)") (class "Default")
      (node (ref "IC3") (pin "12") (pinfunction "K_12") (pintype "input"))
      (node (ref "IC3") (pin "9") (pinfunction "J_9") (pintype "input"))
      (node (ref "IC7") (pin "6") (pinfunction "O_6") (pintype "output"))
    )
    (net (code "61") (name "Net-(IC5A-O)") (class "Default")
      (node (ref "IC5") (pin "3") (pinfunction "O_3") (pintype "output"))
      (node (ref "IC5") (pin "4") (pinfunction "I0_4") (pintype "input"))
      (node (ref "IC5") (pin "9") (pinfunction "I0_9") (pintype "input"))
    )
    (net (code "62") (name "Net-(IC5C-I1)") (class "Default")
      (node (ref "IC5") (pin "10") (pinfunction "I1_10") (pintype "input"))
      (node (ref "IC5") (pin "11") (pinfunction "O_11") (pintype "output"))
    )
    (net (code "63") (name "Net-(IC6A-G1)") (class "Default")
      (node (ref "IC6") (pin "6") (pinfunction "G1_6") (pintype "input"))
      (node (ref "R9") (pin "1") (pinfunction "1_1") (pintype "passive"))
    )
    (net (code "64") (name "Net-(IC7A-O)") (class "Default")
      (node (ref "IC7") (pin "3") (pinfunction "O_3") (pintype "output"))
      (node (ref "IC7") (pin "4") (pinfunction "I0_4") (pintype "input"))
      (node (ref "IC7") (pin "9") (pinfunction "I0_9") (pintype "input"))
    )
    (net (code "65") (name "Net-(IC7C-I1)") (class "Default")
      (node (ref "IC7") (pin "10") (pinfunction "I1_10") (pintype "input"))
      (node (ref "IC7") (pin "11") (pinfunction "O_11") (pintype "output"))
    )
    (net (code "66") (name "Net-(IC11A-C1)") (class "Default")
      (node (ref "IC11") (pin "28") (pinfunction "C1_28") (pintype "input"))
      (node (ref "R12") (pin "1") (pinfunction "1_1") (pintype "passive"))
    )
    (net (code "67") (name "Net-(IC11A-C2)") (class "Default")
      (node (ref "IC11") (pin "4") (pinfunction "C2_4") (pintype "input"))
      (node (ref "R10") (pin "1") (pinfunction "1_1") (pintype "passive"))
    )
    (net (code "68") (name "Net-(IC11A-C3)") (class "Default")
      (node (ref "IC11") (pin "7") (pinfunction "C3_7") (pintype "input"))
      (node (ref "R11") (pin "1") (pinfunction "1_1") (pintype "passive"))
    )
    (net (code "69") (name "Net-(IC11A-CS1)") (class "Default")
      (node (ref "IC11") (pin "16") (pinfunction "CS1_16") (pintype "input"))
      (node (ref "R8") (pin "1") (pinfunction "1_1") (pintype "passive"))
    )
    (net (code "70") (name "Net-(IC12-I1)") (class "Default")
      (node (ref "IC12") (pin "1") (pinfunction "I1_1") (pintype "input"))
      (node (ref "IC12") (pin "2") (pinfunction "I2_2") (pintype "input"))
      (node (ref "IC3") (pin "15") (pinfunction "Q_15") (pintype "output"))
      (node (ref "IC7") (pin "2") (pinfunction "I1_2") (pintype "input"))
    )
    (net (code "71") (name "Net-(IC12-I3)") (class "Default")
      (node (ref "IC12") (pin "3") (pinfunction "I3_3") (pintype "input"))
      (node (ref "IC12") (pin "4") (pinfunction "I4_4") (pintype "input"))
      (node (ref "IC3") (pin "14") (pinfunction "~{Q}_14") (pintype "output"))
    )
    (net (code "72") (name "Net-(IC12-I5)") (class "Default")
      (node (ref "IC12") (pin "5") (pinfunction "I5_5") (pintype "input"))
      (node (ref "IC12") (pin "6") (pinfunction "I6_6") (pintype "input"))
      (node (ref "IC3") (pin "11") (pinfunction "Q_11") (pintype "output"))
    )
    (net (code "73") (name "Net-(IC12-I7)") (class "Default")
      (node (ref "IC12") (pin "7") (pinfunction "I7_7") (pintype "input"))
      (node (ref "IC12") (pin "8") (pinfunction "I8_8") (pintype "input"))
      (node (ref "IC3") (pin "10") (pinfunction "~{Q}_10") (pintype "output"))
      (node (ref "IC7") (pin "1") (pinfunction "I0_1") (pintype "input"))
    )
    (net (code "74") (name "Net-(IC12-O1)") (class "Default")
      (node (ref "IC12") (pin "17") (pinfunction "O2_17") (pintype "open_collector"))
      (node (ref "IC12") (pin "18") (pinfunction "O1_18") (pintype "open_collector"))
      (node (ref "X4") (pin "1") (pinfunction "S_1") (pintype "passive"))
    )
    (net (code "75") (name "Net-(IC12-O3)") (class "Default")
      (node (ref "IC12") (pin "15") (pinfunction "O4_15") (pintype "open_collector"))
      (node (ref "IC12") (pin "16") (pinfunction "O3_16") (pintype "open_collector"))
      (node (ref "X4") (pin "2") (pinfunction "S_2") (pintype "passive"))
    )
    (net (code "76") (name "Net-(IC12-O5)") (class "Default")
      (node (ref "IC12") (pin "13") (pinfunction "O6_13") (pintype "open_collector"))
      (node (ref "IC12") (pin "14") (pinfunction "O5_14") (pintype "open_collector"))
      (node (ref "X4") (pin "3") (pinfunction "S_3") (pintype "passive"))
    )
    (net (code "77") (name "Net-(IC12-O7)") (class "Default")
      (node (ref "IC12") (pin "11") (pinfunction "O8_11") (pintype "open_collector"))
      (node (ref "IC12") (pin "12") (pinfunction "O7_12") (pintype "open_collector"))
      (node (ref "X4") (pin "4") (pinfunction "S_4") (pintype "passive"))
    )
    (net (code "78") (name "Net-(IC13-I1)") (class "Default")
      (node (ref "IC1") (pin "15") (pinfunction "Q_15") (pintype "output"))
      (node (ref "IC13") (pin "1") (pinfunction "I1_1") (pintype "input"))
      (node (ref "IC13") (pin "2") (pinfunction "I2_2") (pintype "input"))
      (node (ref "IC5") (pin "2") (pinfunction "I1_2") (pintype "input"))
    )
    (net (code "79") (name "Net-(IC13-I3)") (class "Default")
      (node (ref "IC1") (pin "14") (pinfunction "~{Q}_14") (pintype "output"))
      (node (ref "IC13") (pin "3") (pinfunction "I3_3") (pintype "input"))
      (node (ref "IC13") (pin "4") (pinfunction "I4_4") (pintype "input"))
    )
    (net (code "80") (name "Net-(IC13-I5)") (class "Default")
      (node (ref "IC1") (pin "11") (pinfunction "Q_11") (pintype "output"))
      (node (ref "IC13") (pin "5") (pinfunction "I5_5") (pintype "input"))
      (node (ref "IC13") (pin "6") (pinfunction "I6_6") (pintype "input"))
    )
    (net (code "81") (name "Net-(IC13-I7)") (class "Default")
      (node (ref "IC1") (pin "10") (pinfunction "~{Q}_10") (pintype "output"))
      (node (ref "IC13") (pin "7") (pinfunction "I7_7") (pintype "input"))
      (node (ref "IC13") (pin "8") (pinfunction "I8_8") (pintype "input"))
      (node (ref "IC5") (pin "1") (pinfunction "I0_1") (pintype "input"))
    )
    (net (code "82") (name "Net-(IC13-O1)") (class "Default")
      (node (ref "IC13") (pin "17") (pinfunction "O2_17") (pintype "open_collector"))
      (node (ref "IC13") (pin "18") (pinfunction "O1_18") (pintype "open_collector"))
      (node (ref "X3") (pin "1") (pinfunction "S_1") (pintype "passive"))
    )
    (net (code "83") (name "Net-(IC13-O3)") (class "Default")
      (node (ref "IC13") (pin "15") (pinfunction "O4_15") (pintype "open_collector"))
      (node (ref "IC13") (pin "16") (pinfunction "O3_16") (pintype "open_collector"))
      (node (ref "X3") (pin "2") (pinfunction "S_2") (pintype "passive"))
    )
    (net (code "84") (name "Net-(IC13-O5)") (class "Default")
      (node (ref "IC13") (pin "13") (pinfunction "O6_13") (pintype "open_collector"))
      (node (ref "IC13") (pin "14") (pinfunction "O5_14") (pintype "open_collector"))
      (node (ref "X3") (pin "3") (pinfunction "S_3") (pintype "passive"))
    )
    (net (code "85") (name "Net-(IC13-O7)") (class "Default")
      (node (ref "IC13") (pin "11") (pinfunction "O8_11") (pintype "open_collector"))
      (node (ref "IC13") (pin "12") (pinfunction "O7_12") (pintype "open_collector"))
      (node (ref "X3") (pin "4") (pinfunction "S_4") (pintype "passive"))
    )
    (net (code "86") (name "Net-(QG1-TS)") (class "Default")
      (node (ref "QG1") (pin "1") (pinfunction "TS_1") (pintype "passive"))
      (node (ref "R1") (pin "1") (pinfunction "1_1") (pintype "passive"))
    )
    (net (code "87") (name "Net-(U1-CS0)") (class "Default")
      (node (ref "R7") (pin "2") (pinfunction "2_2") (pintype "passive"))
      (node (ref "U1") (pin "2") (pinfunction "CS0_2") (pintype "input"))
    )
    (net (code "88") (name "OUT_1") (class "Default")
      (node (ref "SV1") (pin "1") (pinfunction "1_1") (pintype "passive"))
    )
    (net (code "89") (name "OUT_2") (class "Default")
      (node (ref "SV1") (pin "2") (pinfunction "2_2") (pintype "passive"))
    )
    (net (code "90") (name "OUT_3") (class "Default")
      (node (ref "SV1") (pin "3") (pinfunction "3_3") (pintype "passive"))
    )
    (net (code "91") (name "OUT_4") (class "Default")
      (node (ref "SV1") (pin "4") (pinfunction "4_4") (pintype "passive"))
    )
    (net (code "92") (name "PA1") (class "Default")
      (node (ref "IC4") (pin "3") (pinfunction "PA1_3") (pintype "bidirectional"))
    )
    (net (code "93") (name "PA5") (class "Default")
      (node (ref "IC4") (pin "39") (pinfunction "PA5_39") (pintype "bidirectional"))
    )
    (net (code "94") (name "PB0") (class "Default")
      (node (ref "IC4") (pin "18") (pinfunction "PB0_18") (pintype "bidirectional"))
      (node (ref "JP4") (pin "18") (pinfunction "18_18") (pintype "passive"))
    )
    (net (code "95") (name "PB1") (class "Default")
      (node (ref "IC4") (pin "19") (pinfunction "PB1_19") (pintype "bidirectional"))
      (node (ref "JP4") (pin "20") (pinfunction "20_20") (pintype "passive"))
    )
    (net (code "96") (name "PB2") (class "Default")
      (node (ref "IC4") (pin "20") (pinfunction "PB2_20") (pintype "bidirectional"))
      (node (ref "JP4") (pin "22") (pinfunction "22_22") (pintype "passive"))
    )
    (net (code "97") (name "PB3") (class "Default")
      (node (ref "IC4") (pin "21") (pinfunction "PB3_21") (pintype "bidirectional"))
      (node (ref "JP4") (pin "21") (pinfunction "21_21") (pintype "passive"))
    )
    (net (code "98") (name "PB4") (class "Default")
      (node (ref "IC4") (pin "22") (pinfunction "PB4_22") (pintype "bidirectional"))
      (node (ref "JP4") (pin "19") (pinfunction "19_19") (pintype "passive"))
    )
    (net (code "99") (name "PB5") (class "Default")
      (node (ref "IC4") (pin "23") (pinfunction "PB5_23") (pintype "bidirectional"))
      (node (ref "JP4") (pin "17") (pinfunction "17_17") (pintype "passive"))
    )
    (net (code "100") (name "PB6") (class "Default")
      (node (ref "IC4") (pin "24") (pinfunction "PB6_24") (pintype "bidirectional"))
    )
    (net (code "101") (name "PB7") (class "Default")
      (node (ref "IC4") (pin "25") (pinfunction "PB7_25") (pintype "bidirectional"))
    )
    (net (code "102") (name "PC0") (class "Default")
      (node (ref "IC4") (pin "14") (pinfunction "PC0_14") (pintype "bidirectional"))
      (node (ref "JP4") (pin "10") (pinfunction "10_10") (pintype "passive"))
    )
    (net (code "103") (name "PC1") (class "Default")
      (node (ref "IC4") (pin "15") (pinfunction "PC1_15") (pintype "bidirectional"))
      (node (ref "JP4") (pin "12") (pinfunction "12_12") (pintype "passive"))
    )
    (net (code "104") (name "PC2") (class "Default")
      (node (ref "IC4") (pin "16") (pinfunction "PC2_16") (pintype "bidirectional"))
      (node (ref "JP4") (pin "14") (pinfunction "14_14") (pintype "passive"))
    )
    (net (code "105") (name "PC3") (class "Default")
      (node (ref "IC4") (pin "17") (pinfunction "PC3_17") (pintype "bidirectional"))
      (node (ref "JP4") (pin "16") (pinfunction "16_16") (pintype "passive"))
    )
    (net (code "106") (name "PC4") (class "Default")
      (node (ref "IC4") (pin "13") (pinfunction "PC4_13") (pintype "bidirectional"))
      (node (ref "JP4") (pin "8") (pinfunction "8_8") (pintype "passive"))
    )
    (net (code "107") (name "PC5") (class "Default")
      (node (ref "IC4") (pin "12") (pinfunction "PC5_12") (pintype "bidirectional"))
      (node (ref "JP4") (pin "6") (pinfunction "6_6") (pintype "passive"))
    )
    (net (code "108") (name "PC6") (class "Default")
      (node (ref "IC4") (pin "11") (pinfunction "PC6_11") (pintype "bidirectional"))
      (node (ref "JP4") (pin "4") (pinfunction "4_4") (pintype "passive"))
    )
    (net (code "109") (name "PC7") (class "Default")
      (node (ref "IC4") (pin "10") (pinfunction "PC7_10") (pintype "bidirectional"))
      (node (ref "JP4") (pin "2") (pinfunction "2_2") (pintype "passive"))
    )
    (net (code "110") (name "RD") (class "Default")
      (node (ref "CON1") (pin "34") (pinfunction "/IORD_34") (pintype "input"))
      (node (ref "IC4") (pin "5") (pinfunction "RD_5") (pintype "input"))
      (node (ref "SV1") (pin "33") (pinfunction "33_33") (pintype "passive"))
    )
    (net (code "111") (name "RST") (class "Default")
      (node (ref "CON1") (pin "41") (pinfunction "/RESET_41") (pintype "input"))
      (node (ref "IC11") (pin "8") (pinfunction "RESET_8") (pintype "input"))
      (node (ref "IC8") (pin "5") (pinfunction "I_5") (pintype "input"))
      (node (ref "SV1") (pin "29") (pinfunction "29_29") (pintype "passive"))
      (node (ref "U1") (pin "4") (pinfunction "RESB_4") (pintype "input"))
    )
    (net (code "112") (name "RST_INV") (class "Default")
      (node (ref "IC4") (pin "35") (pinfunction "RESET_35") (pintype "input"))
      (node (ref "IC8") (pin "6") (pinfunction "O_6") (pintype "output"))
    )
    (net (code "113") (name "RW") (class "Default")
      (node (ref "IC11") (pin "13") (pinfunction "R/~{W}_13") (pintype "input"))
      (node (ref "SV1") (pin "36") (pinfunction "36_36") (pintype "passive"))
      (node (ref "U1") (pin "28") (pinfunction "R/WB_28") (pintype "input"))
    )
    (net (code "114") (name "STEP1") (class "Default")
      (node (ref "IC1") (pin "1") (pinfunction "CLK_1") (pintype "input"))
      (node (ref "IC1") (pin "6") (pinfunction "CLK_6") (pintype "input"))
      (node (ref "IC11") (pin "3") (pinfunction "O2_3") (pintype "output"))
    )
    (net (code "115") (name "STEP2") (class "Default")
      (node (ref "IC11") (pin "6") (pinfunction "O3_6") (pintype "output"))
      (node (ref "IC3") (pin "1") (pinfunction "CLK_1") (pintype "input"))
      (node (ref "IC3") (pin "6") (pinfunction "CLK_6") (pintype "input"))
    )
    (net (code "116") (name "TIMER_CS") (class "Default")
      (node (ref "IC11") (pin "15") (pinfunction "CS0_15") (pintype "input"))
      (node (ref "IC6") (pin "14") (pinfunction "Y1_14") (pintype "output"))
    )
    (net (code "117") (name "UART_CLK") (class "Default")
      (node (ref "QG1") (pin "8") (pinfunction "OUT_8") (pintype "output"))
      (node (ref "U1") (pin "6") (pinfunction "XTL1_6") (pintype "input"))
    )
    (net (code "118") (name "UART_CS") (class "Default")
      (node (ref "IC6") (pin "13") (pinfunction "Y2_13") (pintype "output"))
      (node (ref "U1") (pin "3") (pinfunction "CS1B_3") (pintype "input"))
    )
    (net (code "119") (name "VCC") (class "Default")
      (node (ref "C1") (pin "1") (pinfunction "1_1") (pintype "passive"))
      (node (ref "C10") (pin "+") (pinfunction "+_+") (pintype "passive"))
      (node (ref "C11") (pin "1") (pinfunction "1_1") (pintype "passive"))
      (node (ref "C12") (pin "1") (pinfunction "1_1") (pintype "passive"))
      (node (ref "C13") (pin "1") (pinfunction "1_1") (pintype "passive"))
      (node (ref "C14") (pin "1") (pinfunction "1_1") (pintype "passive"))
      (node (ref "C15") (pin "1") (pinfunction "1_1") (pintype "passive"))
      (node (ref "C2") (pin "1") (pinfunction "1_1") (pintype "passive"))
      (node (ref "C20") (pin "+") (pinfunction "+_+") (pintype "passive"))
      (node (ref "C3") (pin "1") (pinfunction "1_1") (pintype "passive"))
      (node (ref "C6") (pin "2") (pinfunction "2_2") (pintype "passive"))
      (node (ref "C7") (pin "2") (pinfunction "2_2") (pintype "passive"))
      (node (ref "C8") (pin "1") (pinfunction "1_1") (pintype "passive"))
      (node (ref "C9") (pin "1") (pinfunction "1_1") (pintype "passive"))
      (node (ref "CON1") (pin "13") (pinfunction "VCC2_13") (pintype "power_in"))
      (node (ref "CON1") (pin "38") (pinfunction "VCC1_38") (pintype "power_in"))
      (node (ref "IC1") (pin "2") (pinfunction "PRE_2") (pintype "input"))
      (node (ref "IC1") (pin "3") (pinfunction "CLR_3") (pintype "input"))
      (node (ref "IC1") (pin "5") (pinfunction "VCC_5") (pintype "power_in"))
      (node (ref "IC1") (pin "7") (pinfunction "PRE_7") (pintype "input"))
      (node (ref "IC1") (pin "8") (pinfunction "CLR_8") (pintype "input"))
      (node (ref "IC11") (pin "14") (pinfunction "VCC_14") (pintype "power_in"))
      (node (ref "IC2") (pin "16") (pinfunction "VCC_16") (pintype "power_in"))
      (node (ref "IC3") (pin "2") (pinfunction "PRE_2") (pintype "input"))
      (node (ref "IC3") (pin "3") (pinfunction "CLR_3") (pintype "input"))
      (node (ref "IC3") (pin "5") (pinfunction "VCC_5") (pintype "power_in"))
      (node (ref "IC3") (pin "7") (pinfunction "PRE_7") (pintype "input"))
      (node (ref "IC3") (pin "8") (pinfunction "CLR_8") (pintype "input"))
      (node (ref "IC4") (pin "26") (pinfunction "VCC_26") (pintype "power_in"))
      (node (ref "IC5") (pin "13") (pinfunction "I1_13") (pintype "input"))
      (node (ref "IC5") (pin "14") (pinfunction "VCC_14") (pintype "power_in"))
      (node (ref "IC6") (pin "16") (pinfunction "VCC_16") (pintype "power_in"))
      (node (ref "IC7") (pin "13") (pinfunction "I1_13") (pintype "input"))
      (node (ref "IC7") (pin "14") (pinfunction "VCC_14") (pintype "power_in"))
      (node (ref "IC8") (pin "14") (pinfunction "VCC_14") (pintype "power_in"))
      (node (ref "JP3") (pin "2") (pinfunction "2_2") (pintype "passive"))
      (node (ref "QG1") (pin "14") (pinfunction "VCC_14") (pintype "power_in"))
      (node (ref "R1") (pin "2") (pinfunction "2_2") (pintype "passive"))
      (node (ref "R10") (pin "2") (pinfunction "2_2") (pintype "passive"))
      (node (ref "R11") (pin "2") (pinfunction "2_2") (pintype "passive"))
      (node (ref "R12") (pin "2") (pinfunction "2_2") (pintype "passive"))
      (node (ref "R3") (pin "2") (pinfunction "2_2") (pintype "passive"))
      (node (ref "R4") (pin "2") (pinfunction "2_2") (pintype "passive"))
      (node (ref "R5") (pin "2") (pinfunction "2_2") (pintype "passive"))
      (node (ref "R6") (pin "2") (pinfunction "2_2") (pintype "passive"))
      (node (ref "R7") (pin "1") (pinfunction "1_1") (pintype "passive"))
      (node (ref "R8") (pin "2") (pinfunction "2_2") (pintype "passive"))
      (node (ref "R9") (pin "2") (pinfunction "2_2") (pintype "passive"))
      (node (ref "U1") (pin "15") (pinfunction "VDD_15") (pintype "power_in"))
    )
    (net (code "120") (name "VMOT") (class "Default")
      (node (ref "C16") (pin "+") (pinfunction "+_+") (pintype "passive"))
      (node (ref "C17") (pin "+") (pinfunction "+_+") (pintype "passive"))
      (node (ref "C18") (pin "1") (pinfunction "1_1") (pintype "passive"))
      (node (ref "C19") (pin "1") (pinfunction "1_1") (pintype "passive"))
      (node (ref "IC12") (pin "10") (pinfunction "CD+_10") (pintype "passive"))
      (node (ref "IC13") (pin "10") (pinfunction "CD+_10") (pintype "passive"))
      (node (ref "X3") (pin "5") (pinfunction "S_5") (pintype "passive"))
      (node (ref "X4") (pin "5") (pinfunction "S_5") (pintype "passive"))
      (node (ref "X5") (pin "1") (pinfunction "S_1") (pintype "passive"))
    )
    (net (code "121") (name "WR") (class "Default")
      (node (ref "CON1") (pin "35") (pinfunction "/IOWR_35") (pintype "input"))
      (node (ref "IC4") (pin "36") (pinfunction "WR_36") (pintype "input"))
      (node (ref "SV1") (pin "34") (pinfunction "34_34") (pintype "passive"))
    )
    (net (code "122") (name "unconnected-(CON1A-D08-Pad47)") (class "Default")
      (node (ref "CON1") (pin "47") (pinfunction "D08_47") (pintype "bidirectional"))
    )
    (net (code "123") (name "unconnected-(CON1A-D09-Pad48)") (class "Default")
      (node (ref "CON1") (pin "48") (pinfunction "D09_48") (pintype "bidirectional"))
    )
    (net (code "124") (name "unconnected-(CON1A-D10-Pad49)") (class "Default")
      (node (ref "CON1") (pin "49") (pinfunction "D10_49") (pintype "bidirectional"))
    )
    (net (code "125") (name "unconnected-(CON1A-D11-Pad27)") (class "Default")
      (node (ref "CON1") (pin "27") (pinfunction "D11_27") (pintype "bidirectional"))
    )
    (net (code "126") (name "unconnected-(CON1A-D12-Pad28)") (class "Default")
      (node (ref "CON1") (pin "28") (pinfunction "D12_28") (pintype "bidirectional"))
    )
    (net (code "127") (name "unconnected-(CON1A-D13-Pad29)") (class "Default")
      (node (ref "CON1") (pin "29") (pinfunction "D13_29") (pintype "bidirectional"))
    )
    (net (code "128") (name "unconnected-(CON1A-D14-Pad30)") (class "Default")
      (node (ref "CON1") (pin "30") (pinfunction "D14_30") (pintype "bidirectional"))
    )
    (net (code "129") (name "unconnected-(CON1A-D15-Pad31)") (class "Default")
      (node (ref "CON1") (pin "31") (pinfunction "D15_31") (pintype "bidirectional"))
    )
    (net (code "130") (name "unconnected-(CON1A-INTRQ-Pad37)") (class "Default")
      (node (ref "CON1") (pin "37") (pinfunction "INTRQ_37") (pintype "output"))
    )
    (net (code "131") (name "unconnected-(CON1A-IORDY-Pad42)") (class "Default")
      (node (ref "CON1") (pin "42") (pinfunction "IORDY_42") (pintype "output"))
    )
    (net (code "132") (name "unconnected-(CON1A-{slash}CD1-Pad26)") (class "Default")
      (node (ref "CON1") (pin "26") (pinfunction "/CD1_26") (pintype "output"))
    )
    (net (code "133") (name "unconnected-(CON1A-{slash}CD2-Pad25)") (class "Default")
      (node (ref "CON1") (pin "25") (pinfunction "/CD2_25") (pintype "output"))
    )
    (net (code "134") (name "unconnected-(CON1A-{slash}DASP-Pad45)") (class "Default")
      (node (ref "CON1") (pin "45") (pinfunction "/DASP_45") (pintype "bidirectional"))
    )
    (net (code "135") (name "unconnected-(CON1A-{slash}INPACK-Pad43)") (class "Default")
      (node (ref "CON1") (pin "43") (pinfunction "/INPACK_43") (pintype "output"))
    )
    (net (code "136") (name "unconnected-(CON1A-{slash}IOCS16-Pad24)") (class "Default")
      (node (ref "CON1") (pin "24") (pinfunction "/IOCS16_24") (pintype "output"))
    )
    (net (code "137") (name "unconnected-(CON1A-{slash}VS1-Pad33)") (class "Default")
      (node (ref "CON1") (pin "33") (pinfunction "/VS1_33") (pintype "output"))
    )
    (net (code "138") (name "unconnected-(CON1A-{slash}VS2-Pad40)") (class "Default")
      (node (ref "CON1") (pin "40") (pinfunction "/VS2_40") (pintype "output"))
    )
    (net (code "139") (name "unconnected-(IC2A-R2OUT-Pad9)") (class "Default")
      (node (ref "IC2") (pin "9") (pinfunction "R2OUT_9") (pintype "output"))
    )
    (net (code "140") (name "unconnected-(IC2A-T2IN-Pad10)") (class "Default")
      (node (ref "IC2") (pin "10") (pinfunction "T2IN_10") (pintype "input"))
    )
    (net (code "141") (name "unconnected-(IC4A-PA4-Pad40)") (class "Default")
      (node (ref "IC4") (pin "40") (pinfunction "PA4_40") (pintype "bidirectional"))
    )
    (net (code "142") (name "unconnected-(IC6A-Y4-Pad11)") (class "Default")
      (node (ref "IC6") (pin "11") (pinfunction "Y4_11") (pintype "output"))
    )
    (net (code "143") (name "unconnected-(IC6A-Y5-Pad10)") (class "Default")
      (node (ref "IC6") (pin "10") (pinfunction "Y5_10") (pintype "output"))
    )
    (net (code "144") (name "unconnected-(IC6A-Y6-Pad9)") (class "Default")
      (node (ref "IC6") (pin "9") (pinfunction "Y6_9") (pintype "output"))
    )
    (net (code "145") (name "unconnected-(IC6A-Y7-Pad7)") (class "Default")
      (node (ref "IC6") (pin "7") (pinfunction "Y7_7") (pintype "output"))
    )
    (net (code "146") (name "unconnected-(IC8A-O-Pad2)") (class "Default")
      (node (ref "IC8") (pin "2") (pinfunction "O_2") (pintype "output"))
    )
    (net (code "147") (name "unconnected-(IC8B-O-Pad4)") (class "Default")
      (node (ref "IC8") (pin "4") (pinfunction "O_4") (pintype "output"))
    )
    (net (code "148") (name "unconnected-(IC8D-O-Pad8)") (class "Default")
      (node (ref "IC8") (pin "8") (pinfunction "O_8") (pintype "output"))
    )
    (net (code "149") (name "unconnected-(IC8E-O-Pad10)") (class "Default")
      (node (ref "IC8") (pin "10") (pinfunction "O_10") (pintype "output"))
    )
    (net (code "150") (name "unconnected-(IC8F-O-Pad12)") (class "Default")
      (node (ref "IC8") (pin "12") (pinfunction "O_12") (pintype "output"))
    )
    (net (code "151") (name "unconnected-(IC11A-O1-Pad27)") (class "Default")
      (node (ref "IC11") (pin "27") (pinfunction "O1_27") (pintype "output"))
    )
    (net (code "152") (name "unconnected-(U1-DTR-Pad11)") (class "Default")
      (node (ref "U1") (pin "11") (pinfunction "DTR_11") (pintype "output"))
    )
    (net (code "153") (name "unconnected-(U1-RTS-Pad8)") (class "Default")
      (node (ref "U1") (pin "8") (pinfunction "RTS_8") (pintype "output"))
    )
    (net (code "154") (name "unconnected-(U1-RXCLK-Pad5)") (class "Default")
      (node (ref "U1") (pin "5") (pinfunction "RXCLK_5") (pintype "bidirectional"))
    )
    (net (code "155") (name "unconnected-(U1-XTL2-Pad7)") (class "Default")
      (node (ref "U1") (pin "7") (pinfunction "XTL2_7") (pintype "output"))
    )
    (net (code "156") (name "unconnected-(X1-Pad1)") (class "Default")
      (node (ref "X1") (pin "1") (pinfunction "1_1") (pintype "passive"))
    )
    (net (code "157") (name "unconnected-(X1-Pad4)") (class "Default")
      (node (ref "X1") (pin "4") (pinfunction "4_4") (pintype "passive"))
    )
    (net (code "158") (name "unconnected-(X1-Pad6)") (class "Default")
      (node (ref "X1") (pin "6") (pinfunction "6_6") (pintype "passive"))
    )
    (net (code "159") (name "unconnected-(X1-Pad9)") (class "Default")
      (node (ref "X1") (pin "9") (pinfunction "9_9") (pintype "passive"))
    )
  )
)
